# jacarerele2.net
KiCad netlist of a schematic drawn in EAGLE
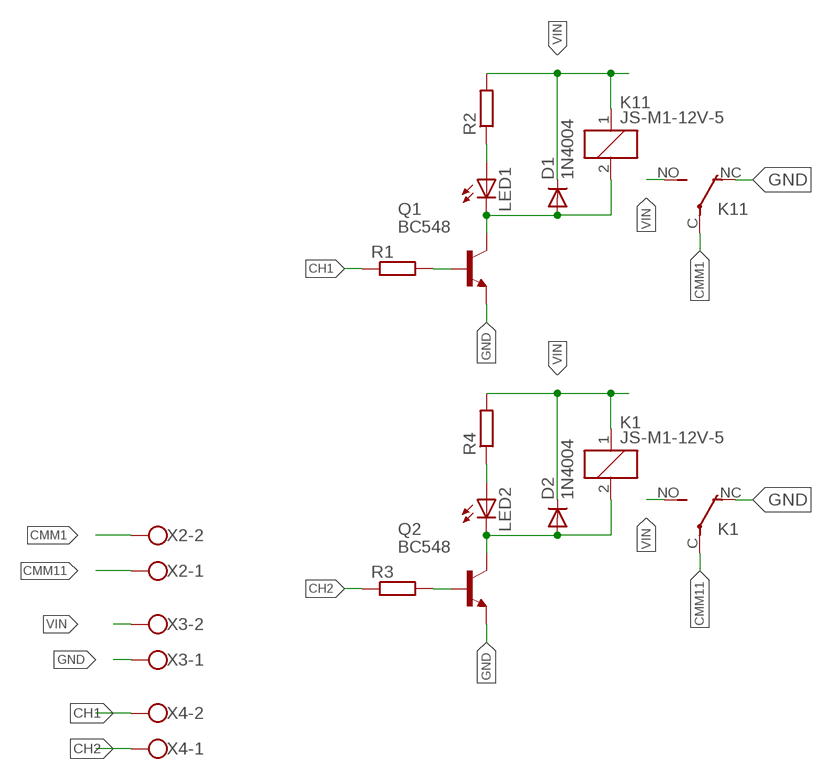
[diagram p0: schematic, sheet 1]

(export (version "E")
  (design (tool "Eeschema 10.0.6"))
  (components
    (comp (ref "D1")
      (value "1N4004")
      (footprint "eagle-import:DO41-10")
      (libsource (lib "eagle-import") (part "1N4004"))
    )
    (comp (ref "D2")
      (value "1N4004")
      (footprint "eagle-import:DO41-10")
      (libsource (lib "eagle-import") (part "1N4004"))
    )
    (comp (ref "K1")
      (value "JS-M1-12V-5")
      (footprint "eagle-import:JS-M")
      (fields (field (name "MF") "FARNELL") (field (name "MPN") "JSM1-12V-5"))
      (libsource (lib "eagle-import") (part "JS-M1-12V-5"))
    )
    (comp (ref "K11")
      (value "JS-M1-12V-5")
      (footprint "eagle-import:JS-M")
      (fields (field (name "MF") "FARNELL") (field (name "MPN") "JSM1-12V-5"))
      (libsource (lib "eagle-import") (part "JS-M1-12V-5"))
    )
    (comp (ref "LED1")
      (value "LED5MM")
      (footprint "eagle-import:LED5MM")
      (libsource (lib "eagle-import") (part "LED5MM"))
    )
    (comp (ref "LED2")
      (value "LED5MM")
      (footprint "eagle-import:LED5MM")
      (libsource (lib "eagle-import") (part "LED5MM"))
    )
    (comp (ref "Q1")
      (value "BC548")
      (footprint "eagle-import:TO92-EBC")
      (libsource (lib "eagle-import") (part "BC548"))
    )
    (comp (ref "Q2")
      (value "BC548")
      (footprint "eagle-import:TO92-EBC")
      (libsource (lib "eagle-import") (part "BC548"))
    )
    (comp (ref "R1")
      (value "R-EU_0207/10")
      (footprint "eagle-import:0207_10")
      (libsource (lib "eagle-import") (part "R-EU_0207/10"))
    )
    (comp (ref "R2")
      (value "R-EU_0207/10")
      (footprint "eagle-import:0207_10")
      (libsource (lib "eagle-import") (part "R-EU_0207/10"))
    )
    (comp (ref "R3")
      (value "R-EU_0207/10")
      (footprint "eagle-import:0207_10")
      (libsource (lib "eagle-import") (part "R-EU_0207/10"))
    )
    (comp (ref "R4")
      (value "R-EU_0207/10")
      (footprint "eagle-import:0207_10")
      (libsource (lib "eagle-import") (part "R-EU_0207/10"))
    )
    (comp (ref "X2")
      (value "W237-102")
      (footprint "eagle-import:W237-102")
      (fields (field (name "MPN") "237-102"))
      (libsource (lib "eagle-import") (part "W237-102"))
    )
    (comp (ref "X3")
      (value "W237-102")
      (footprint "eagle-import:W237-102")
      (fields (field (name "MPN") "237-102"))
      (libsource (lib "eagle-import") (part "W237-102"))
    )
    (comp (ref "X4")
      (value "W237-102")
      (footprint "eagle-import:W237-102")
      (fields (field (name "MPN") "237-102"))
      (libsource (lib "eagle-import") (part "W237-102"))
    )
  )
  (nets
    (net (code "1") (name "CH1") (class "Default")
      (node (ref "R1") (pin "1") (pinfunction "1_1") (pintype "passive"))
      (node (ref "X4") (pin "2") (pinfunction "KL_2") (pintype "passive"))
    )
    (net (code "2") (name "CH2") (class "Default")
      (node (ref "R3") (pin "1") (pinfunction "1_1") (pintype "passive"))
      (node (ref "X4") (pin "1") (pinfunction "KL_1") (pintype "passive"))
    )
    (net (code "3") (name "CMM1") (class "Default")
      (node (ref "K11") (pin "C") (pinfunction "P_C") (pintype "passive"))
      (node (ref "X2") (pin "2") (pinfunction "KL_2") (pintype "passive"))
    )
    (net (code "4") (name "CMM11") (class "Default")
      (node (ref "K1") (pin "C") (pinfunction "P_C") (pintype "passive"))
      (node (ref "X2") (pin "1") (pinfunction "KL_1") (pintype "passive"))
    )
    (net (code "5") (name "GND") (class "Default")
      (node (ref "K1") (pin "NC") (pinfunction "O_NC") (pintype "passive"))
      (node (ref "K11") (pin "NC") (pinfunction "O_NC") (pintype "passive"))
      (node (ref "Q1") (pin "E") (pinfunction "E_E") (pintype "passive"))
      (node (ref "Q2") (pin "E") (pinfunction "E_E") (pintype "passive"))
      (node (ref "X3") (pin "1") (pinfunction "KL_1") (pintype "passive"))
    )
    (net (code "6") (name "Net-(LED1-C)") (class "Default")
      (node (ref "D1") (pin "A") (pinfunction "A_A") (pintype "passive"))
      (node (ref "K11") (pin "2") (pinfunction "2_2") (pintype "passive"))
      (node (ref "LED1") (pin "K") (pinfunction "C_K") (pintype "passive"))
      (node (ref "Q1") (pin "C") (pinfunction "C_C") (pintype "passive"))
    )
    (net (code "7") (name "Net-(LED1-PadA)") (class "Default")
      (node (ref "LED1") (pin "A") (pinfunction "A_A") (pintype "passive"))
      (node (ref "R2") (pin "1") (pinfunction "1_1") (pintype "passive"))
    )
    (net (code "8") (name "Net-(LED2-C)") (class "Default")
      (node (ref "D2") (pin "A") (pinfunction "A_A") (pintype "passive"))
      (node (ref "K1") (pin "2") (pinfunction "2_2") (pintype "passive"))
      (node (ref "LED2") (pin "K") (pinfunction "C_K") (pintype "passive"))
      (node (ref "Q2") (pin "C") (pinfunction "C_C") (pintype "passive"))
    )
    (net (code "9") (name "Net-(LED2-PadA)") (class "Default")
      (node (ref "LED2") (pin "A") (pinfunction "A_A") (pintype "passive"))
      (node (ref "R4") (pin "1") (pinfunction "1_1") (pintype "passive"))
    )
    (net (code "10") (name "Net-(Q1-PadB)") (class "Default")
      (node (ref "Q1") (pin "B") (pinfunction "B_B") (pintype "passive"))
      (node (ref "R1") (pin "2") (pinfunction "2_2") (pintype "passive"))
    )
    (net (code "11") (name "Net-(Q2-PadB)") (class "Default")
      (node (ref "Q2") (pin "B") (pinfunction "B_B") (pintype "passive"))
      (node (ref "R3") (pin "2") (pinfunction "2_2") (pintype "passive"))
    )
    (net (code "12") (name "VIN") (class "Default")
      (node (ref "D1") (pin "C") (pinfunction "C_C") (pintype "passive"))
      (node (ref "D2") (pin "C") (pinfunction "C_C") (pintype "passive"))
      (node (ref "K1") (pin "1") (pinfunction "1_1") (pintype "passive"))
      (node (ref "K1") (pin "NO") (pinfunction "S_NO") (pintype "passive"))
      (node (ref "K11") (pin "1") (pinfunction "1_1") (pintype "passive"))
      (node (ref "K11") (pin "NO") (pinfunction "S_NO") (pintype "passive"))
      (node (ref "R2") (pin "2") (pinfunction "2_2") (pintype "passive"))
      (node (ref "R4") (pin "2") (pinfunction "2_2") (pintype "passive"))
      (node (ref "X3") (pin "2") (pinfunction "KL_2") (pintype "passive"))
    )
  )
)
